# MDL_RECEPTOR_IRF_1.net
KiCad netlist of a schematic drawn in Altium Designer
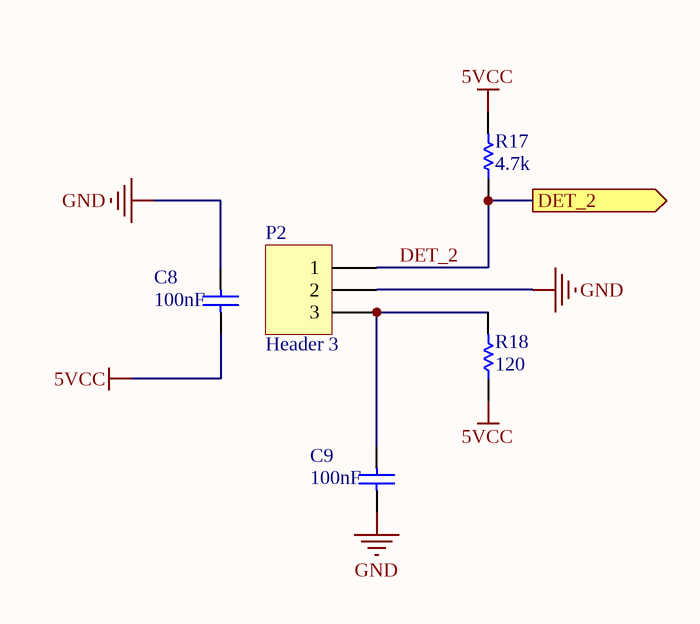
[diagram p0: MDL_RECEPTOR_IRF_1.SchDoc]

(export (version "E")
  (design (tool "Eeschema 10.0.6"))
  (components
    (comp (ref "C8")
      (value "100nF")
      (footprint "VP44-2.5")
      (description "Dipped Radial Multilayer Ceramic Capacitor X7R: 220nF, 100V")
      (fields (field (name "Comment") "VP44BY224JB") (field (name "PUBLISHER") "Altium Limited"))
      (libsource (lib "Vishay Vitramon Ceramic Dipped Capacitor") (part "VP44BY224JB"))
    )
    (comp (ref "C9")
      (value "100nF")
      (footprint "VP44-2.5")
      (description "Dipped Radial Multilayer Ceramic Capacitor X7R: 220nF, 100V")
      (fields (field (name "Comment") "VP44BY224JB") (field (name "PUBLISHER") "Altium Limited"))
      (libsource (lib "Vishay Vitramon Ceramic Dipped Capacitor") (part "VP44BY224JB"))
    )
    (comp (ref "P2")
      (value "Header 3")
      (footprint "HDR1X3")
      (description "Header, 3-Pin")
      (fields (field (name "PUBLISHER") "Altium Limited"))
      (libsource (lib "Miscellaneous Connectors") (part "Header 3"))
    )
    (comp (ref "R17")
      (value "4.7k")
      (footprint "AXIAL-0.3")
      (description "Resistor")
      (fields (field (name "Comment") "Res") (field (name "PUBLISHER") "Altium Limited"))
      (libsource (lib "Miscellaneous Devices") (part "Res1"))
    )
    (comp (ref "R18")
      (value "120")
      (footprint "AXIAL-0.3")
      (description "Resistor")
      (fields (field (name "Comment") "Res") (field (name "PUBLISHER") "Altium Limited"))
      (libsource (lib "Miscellaneous Devices") (part "Res1"))
    )
  )
  (nets
    (net (code "1") (name "/DET_2") (class "Default")
      (node (ref "P2") (pin "1") (pinfunction "1_1") (pintype "passive"))
      (node (ref "R17") (pin "1") (pinfunction "1_1") (pintype "passive"))
    )
    (net (code "2") (name "5VCC") (class "Default")
      (node (ref "C8") (pin "2") (pinfunction "2_2") (pintype "passive"))
      (node (ref "R17") (pin "2") (pinfunction "2_2") (pintype "passive"))
      (node (ref "R18") (pin "1") (pinfunction "1_1") (pintype "passive"))
    )
    (net (code "3") (name "GND") (class "Default")
      (node (ref "C8") (pin "1") (pinfunction "1_1") (pintype "passive"))
      (node (ref "C9") (pin "2") (pinfunction "2_2") (pintype "passive"))
      (node (ref "P2") (pin "2") (pinfunction "2_2") (pintype "passive"))
    )
    (net (code "4") (name "Net-(C9-Pad1)") (class "Default")
      (node (ref "C9") (pin "1") (pinfunction "1_1") (pintype "passive"))
      (node (ref "P2") (pin "3") (pinfunction "3_3") (pintype "passive"))
      (node (ref "R18") (pin "2") (pinfunction "2_2") (pintype "passive"))
    )
  )
)
